# DUT.net
KiCad netlist of a schematic drawn in Altium Designer
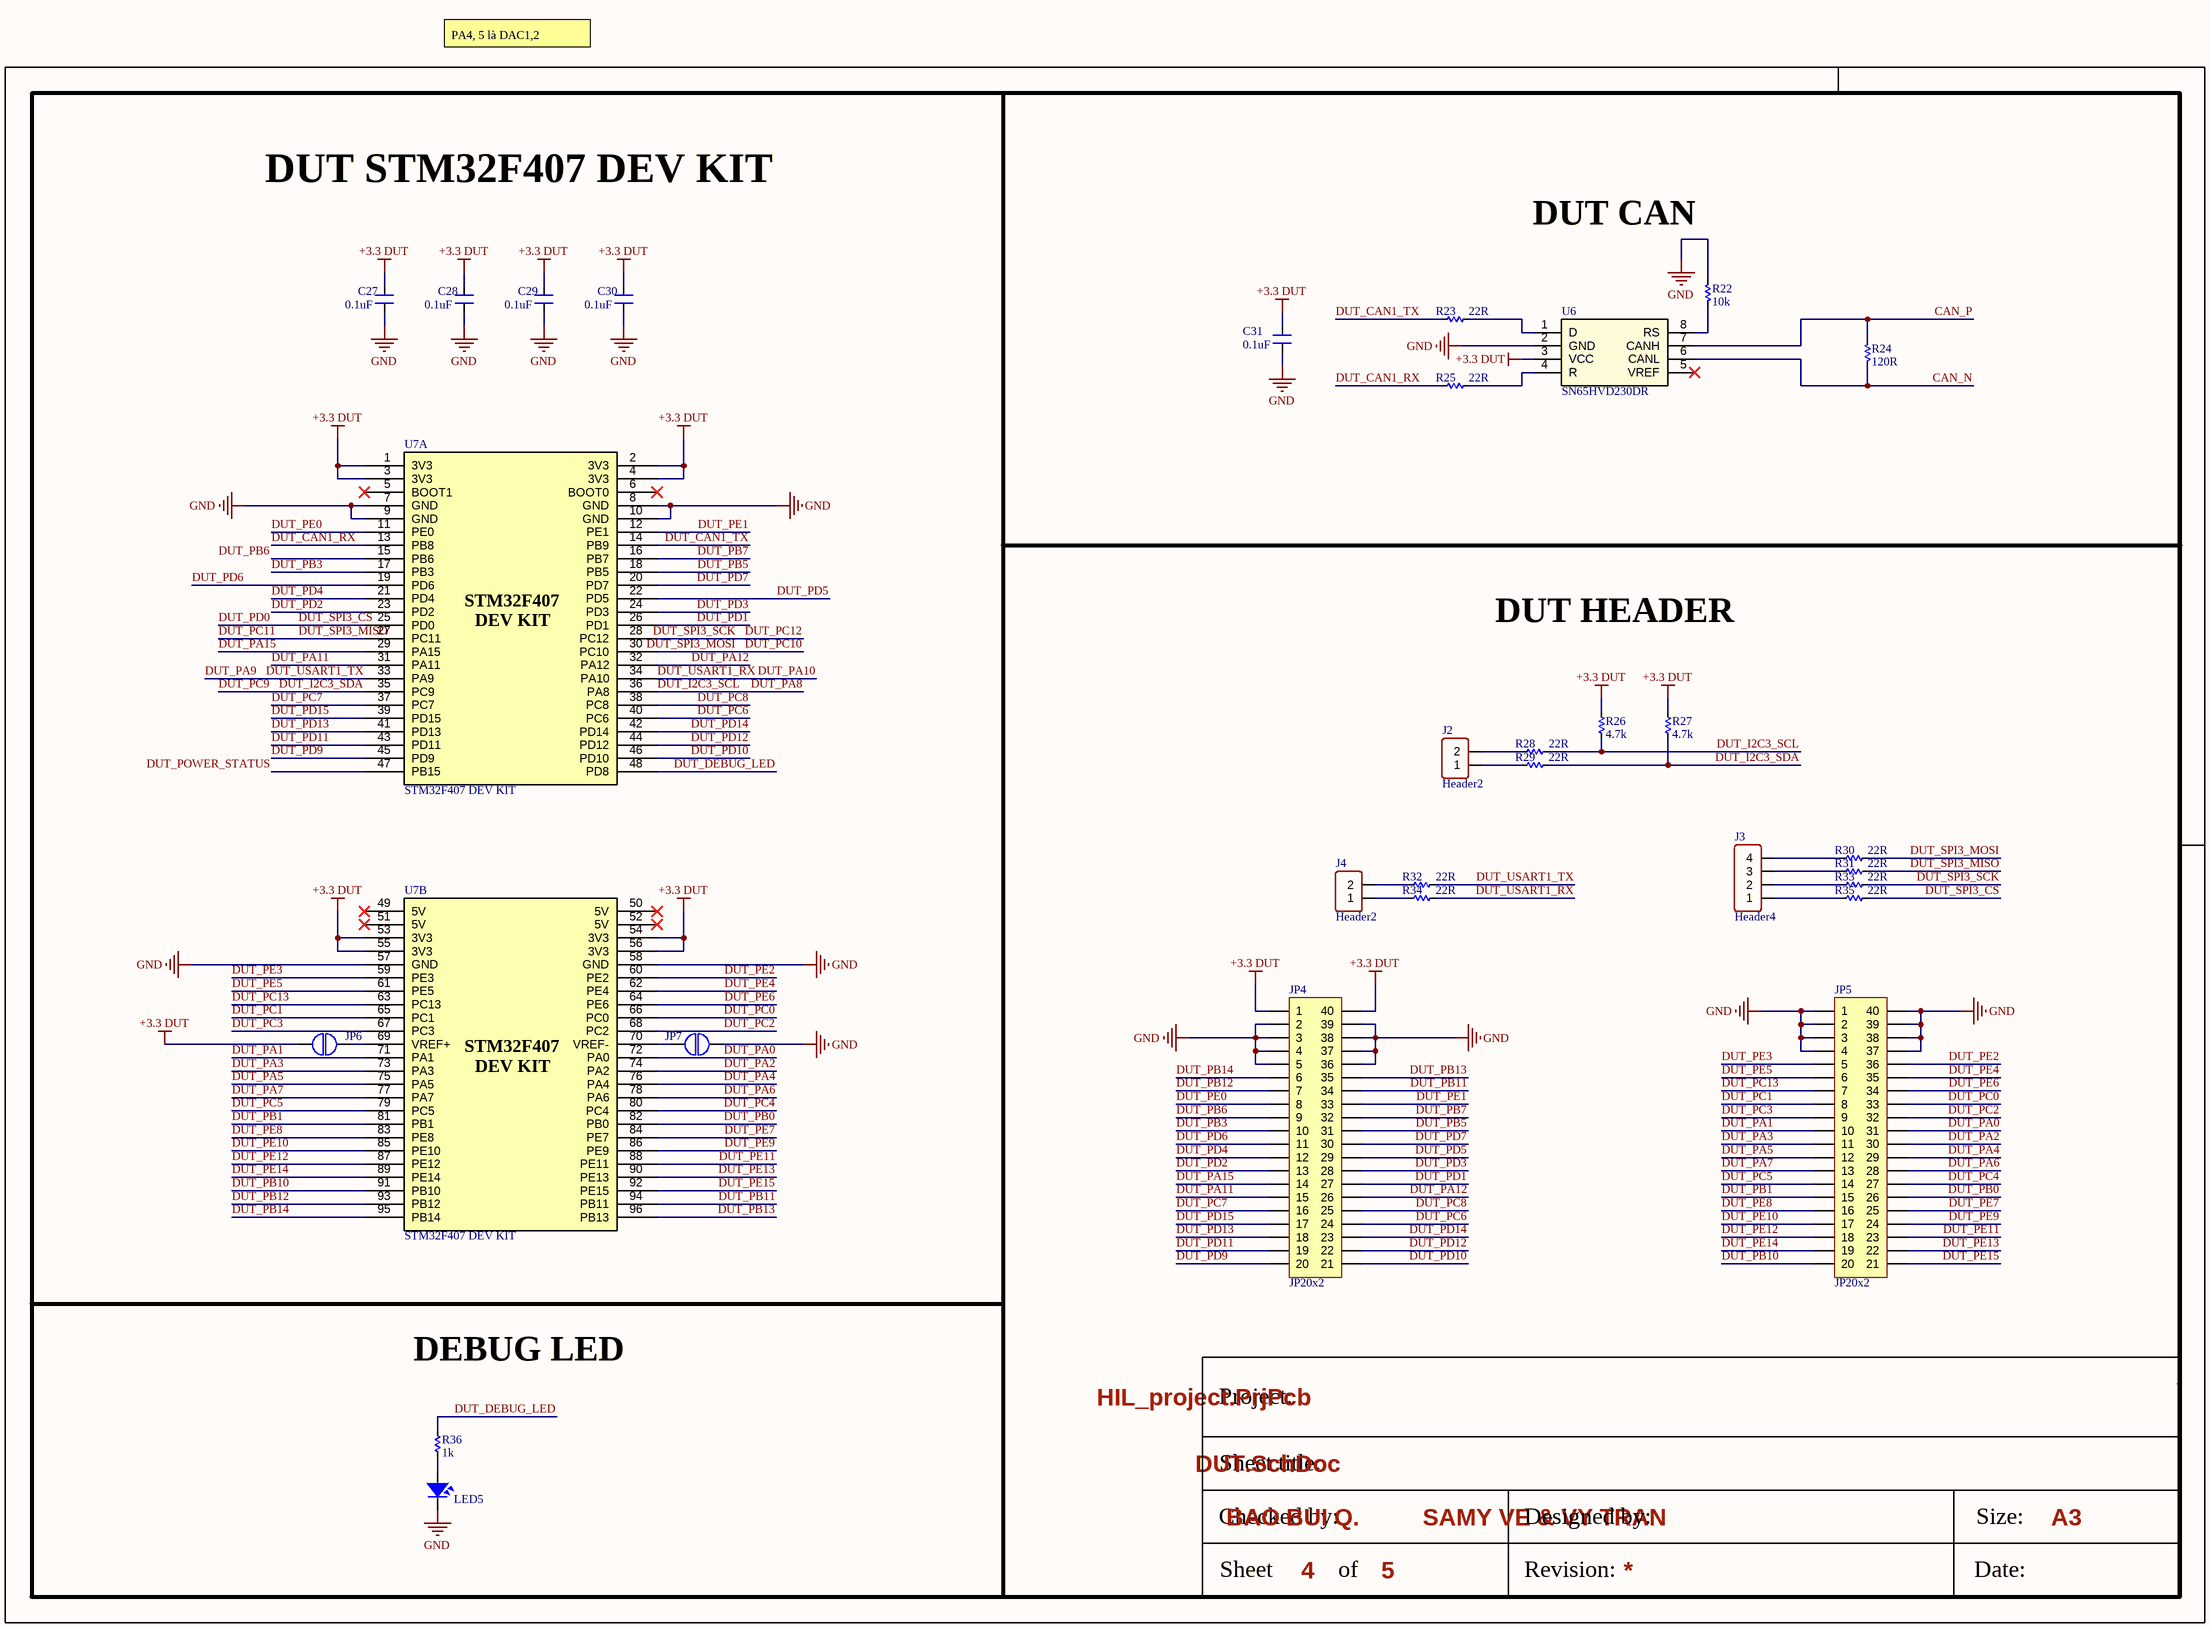
[diagram p0: DUT.SchDoc]

(export (version "E")
  (design (tool "Eeschema 10.0.6"))
  (components
    (comp (ref "C27") (value "0.1uF") (footprint "CN-SMD-0603") (libsource (lib "Library") (part "CN")))
    (comp (ref "C28") (value "0.1uF") (footprint "CN-SMD-0603") (libsource (lib "Library") (part "CN")))
    (comp (ref "C29") (value "0.1uF") (footprint "CN-SMD-0603") (libsource (lib "Library") (part "CN")))
    (comp (ref "C30") (value "0.1uF") (footprint "CN-SMD-0603") (libsource (lib "Library") (part "CN")))
    (comp (ref "C31") (value "0.1uF") (footprint "CN-SMD-0603") (libsource (lib "Library") (part "CN")))
    (comp (ref "J2")
      (value "Header2")
      (footprint "XH2.54-2-DIP")
      (description "Connector 2")
      (fields
        (field (name "MANUFACTURER") "Würth Elektronik eiSos GmbH")
        (field (name "PARTNO") "613002143121")
        (field (name "CREATED BY") "Karrer Zheng")
      )
      (libsource (lib "Library") (part "Header2"))
    )
    (comp (ref "J3")
      (value "Header4")
      (footprint "XH2.54-4-DIP")
      (description "Connector 4")
      (fields
        (field (name "MANUFACTURER") "Würth Elektronik eiSos GmbH")
        (field (name "PARTNO") "613002143121")
        (field (name "CREATED BY") "Karrer Zheng")
      )
      (libsource (lib "Library") (part "Header4"))
    )
    (comp (ref "J4")
      (value "Header2")
      (footprint "XH2.54-2-DIP")
      (description "Connector 2")
      (fields
        (field (name "MANUFACTURER") "Würth Elektronik eiSos GmbH")
        (field (name "PARTNO") "613002143121")
        (field (name "CREATED BY") "Karrer Zheng")
      )
      (libsource (lib "Library") (part "Header2"))
    )
    (comp (ref "JP4")
      (value "JP20x2")
      (footprint "JP20-D2T")
      (description "WR-PHD 2.54 mm Dual Socket Header")
      (fields
        (field (name "MANUFACTURER") "Würth Elektronik eiSos GmbH")
        (field (name "PARTNO") "61304021821")
        (field (name "CREATED BY") "Karrer Zheng")
      )
      (libsource (lib "Library") (part "JP20x2"))
    )
    (comp (ref "JP5")
      (value "JP20x2")
      (footprint "JP20-D2T")
      (description "WR-PHD 2.54 mm Dual Socket Header")
      (fields
        (field (name "MANUFACTURER") "Würth Elektronik eiSos GmbH")
        (field (name "PARTNO") "61304021821")
        (field (name "CREATED BY") "Karrer Zheng")
      )
      (libsource (lib "Library") (part "JP20x2"))
    )
    (comp (ref "JP6") (value "JUMP2") (footprint "Jump2") (libsource (lib "Library") (part "JUMP2")))
    (comp (ref "JP7") (value "JUMP2") (footprint "Jump2") (libsource (lib "Library") (part "JUMP2")))
    (comp (ref "LED5") (value "LED") (footprint "LED-0805-Red") (libsource (lib "Library") (part "LED SMD")))
    (comp (ref "R22")
      (value "10k")
      (footprint "RES-SMD-0603")
      (description "Resistor")
      (fields
        (field (name "MANUFACTURER") "Generic Components")
        (field (name "PUBLISHER") "Altium Hobart Technology Centre")
      )
      (libsource (lib "Library") (part "Res-SMD"))
    )
    (comp (ref "R23")
      (value "22R")
      (footprint "RES-SMD-0603")
      (description "Resistor")
      (fields
        (field (name "MANUFACTURER") "Generic Components")
        (field (name "PUBLISHER") "Altium Hobart Technology Centre")
      )
      (libsource (lib "Library") (part "Res-SMD"))
    )
    (comp (ref "R24")
      (value "120R")
      (footprint "RES-SMD-0603")
      (description "Resistor")
      (fields
        (field (name "MANUFACTURER") "Generic Components")
        (field (name "PUBLISHER") "Altium Hobart Technology Centre")
      )
      (libsource (lib "Library") (part "Res-SMD"))
    )
    (comp (ref "R25")
      (value "22R")
      (footprint "RES-SMD-0603")
      (description "Resistor")
      (fields
        (field (name "MANUFACTURER") "Generic Components")
        (field (name "PUBLISHER") "Altium Hobart Technology Centre")
      )
      (libsource (lib "Library") (part "Res-SMD"))
    )
    (comp (ref "R26")
      (value "4.7k")
      (footprint "RES-SMD-0603")
      (description "Resistor")
      (fields
        (field (name "MANUFACTURER") "Generic Components")
        (field (name "PUBLISHER") "Altium Hobart Technology Centre")
      )
      (libsource (lib "Library") (part "Res-SMD"))
    )
    (comp (ref "R27")
      (value "4.7k")
      (footprint "RES-SMD-0603")
      (description "Resistor")
      (fields
        (field (name "MANUFACTURER") "Generic Components")
        (field (name "PUBLISHER") "Altium Hobart Technology Centre")
      )
      (libsource (lib "Library") (part "Res-SMD"))
    )
    (comp (ref "R28")
      (value "22R")
      (footprint "RES-SMD-0603")
      (description "Resistor")
      (fields
        (field (name "MANUFACTURER") "Generic Components")
        (field (name "PUBLISHER") "Altium Hobart Technology Centre")
      )
      (libsource (lib "Library") (part "Res-SMD"))
    )
    (comp (ref "R29")
      (value "22R")
      (footprint "RES-SMD-0603")
      (description "Resistor")
      (fields
        (field (name "MANUFACTURER") "Generic Components")
        (field (name "PUBLISHER") "Altium Hobart Technology Centre")
      )
      (libsource (lib "Library") (part "Res-SMD"))
    )
    (comp (ref "R30")
      (value "22R")
      (footprint "RES-SMD-0603")
      (description "Resistor")
      (fields
        (field (name "MANUFACTURER") "Generic Components")
        (field (name "PUBLISHER") "Altium Hobart Technology Centre")
      )
      (libsource (lib "Library") (part "Res-SMD"))
    )
    (comp (ref "R31")
      (value "22R")
      (footprint "RES-SMD-0603")
      (description "Resistor")
      (fields
        (field (name "MANUFACTURER") "Generic Components")
        (field (name "PUBLISHER") "Altium Hobart Technology Centre")
      )
      (libsource (lib "Library") (part "Res-SMD"))
    )
    (comp (ref "R32")
      (value "22R")
      (footprint "RES-SMD-0603")
      (description "Resistor")
      (fields
        (field (name "MANUFACTURER") "Generic Components")
        (field (name "PUBLISHER") "Altium Hobart Technology Centre")
      )
      (libsource (lib "Library") (part "Res-SMD"))
    )
    (comp (ref "R33")
      (value "22R")
      (footprint "RES-SMD-0603")
      (description "Resistor")
      (fields
        (field (name "MANUFACTURER") "Generic Components")
        (field (name "PUBLISHER") "Altium Hobart Technology Centre")
      )
      (libsource (lib "Library") (part "Res-SMD"))
    )
    (comp (ref "R34")
      (value "22R")
      (footprint "RES-SMD-0603")
      (description "Resistor")
      (fields
        (field (name "MANUFACTURER") "Generic Components")
        (field (name "PUBLISHER") "Altium Hobart Technology Centre")
      )
      (libsource (lib "Library") (part "Res-SMD"))
    )
    (comp (ref "R35")
      (value "22R")
      (footprint "RES-SMD-0603")
      (description "Resistor")
      (fields
        (field (name "MANUFACTURER") "Generic Components")
        (field (name "PUBLISHER") "Altium Hobart Technology Centre")
      )
      (libsource (lib "Library") (part "Res-SMD"))
    )
    (comp (ref "R36")
      (value "1k")
      (footprint "RES-SMD-0603")
      (description "Resistor")
      (fields
        (field (name "MANUFACTURER") "Generic Components")
        (field (name "PUBLISHER") "Altium Hobart Technology Centre")
      )
      (libsource (lib "Library") (part "Res-SMD"))
    )
    (comp (ref "U6")
      (value "SN65HVD230DR")
      (footprint "SO8")
      (description "IC TRANSCEIVER HALF 1/1 8SOIC")
      (libsource (lib "Library") (part "SN65HVD251DR"))
    )
    (comp (ref "U7")
      (value "STM32F407 DEV KIT")
      (footprint "STM32F407 DEV KIT")
      (libsource (lib "Library") (part "STM32F407 DEV KIT"))
    )
  )
  (nets
    (net (code "1") (name "+3.3 DUT") (class "Default")
      (node (ref "C27") (pin "1") (pinfunction "1_1") (pintype "passive"))
      (node (ref "C28") (pin "1") (pinfunction "1_1") (pintype "passive"))
      (node (ref "C29") (pin "1") (pinfunction "1_1") (pintype "passive"))
      (node (ref "C30") (pin "1") (pinfunction "1_1") (pintype "passive"))
      (node (ref "C31") (pin "1") (pinfunction "1_1") (pintype "passive"))
      (node (ref "JP4") (pin "1") (pinfunction "1_1") (pintype "passive"))
      (node (ref "JP4") (pin "40") (pinfunction "40_40") (pintype "passive"))
      (node (ref "JP6") (pin "1") (pinfunction "1_1") (pintype "passive"))
      (node (ref "R26") (pin "1") (pinfunction "1_1") (pintype "passive"))
      (node (ref "R27") (pin "1") (pinfunction "1_1") (pintype "passive"))
      (node (ref "U6") (pin "3") (pinfunction "VCC_3") (pintype "power_in"))
      (node (ref "U7") (pin "1") (pinfunction "3V3_1") (pintype "passive"))
      (node (ref "U7") (pin "2") (pinfunction "3V3_2") (pintype "passive"))
      (node (ref "U7") (pin "3") (pinfunction "3V3_3") (pintype "passive"))
      (node (ref "U7") (pin "4") (pinfunction "3V3_4") (pintype "passive"))
      (node (ref "U7") (pin "53") (pinfunction "3V3_53") (pintype "passive"))
      (node (ref "U7") (pin "54") (pinfunction "3V3_54") (pintype "passive"))
      (node (ref "U7") (pin "55") (pinfunction "3V3_55") (pintype "passive"))
      (node (ref "U7") (pin "56") (pinfunction "3V3_56") (pintype "passive"))
    )
    (net (code "2") (name "/CAN_N") (class "Default")
      (node (ref "R24") (pin "2") (pinfunction "2_2") (pintype "passive"))
      (node (ref "U6") (pin "6") (pinfunction "CANL_6") (pintype "power_in"))
    )
    (net (code "3") (name "/CAN_P") (class "Default")
      (node (ref "R24") (pin "1") (pinfunction "1_1") (pintype "passive"))
      (node (ref "U6") (pin "7") (pinfunction "CANH_7") (pintype "power_in"))
    )
    (net (code "4") (name "/DUT_CAN1_RX") (class "Default")
      (node (ref "R25") (pin "2") (pinfunction "2_2") (pintype "passive"))
      (node (ref "U7") (pin "13") (pinfunction "PB8_13") (pintype "passive"))
    )
    (net (code "5") (name "/DUT_CAN1_TX") (class "Default")
      (node (ref "R23") (pin "2") (pinfunction "2_2") (pintype "passive"))
      (node (ref "U7") (pin "14") (pinfunction "PB9_14") (pintype "passive"))
    )
    (net (code "6") (name "/DUT_DEBUG_LED") (class "Default")
      (node (ref "R36") (pin "2") (pinfunction "2_2") (pintype "passive"))
      (node (ref "U7") (pin "48") (pinfunction "PD8_48") (pintype "passive"))
    )
    (net (code "7") (name "/DUT_I2C3_SCL") (class "Default")
      (node (ref "R26") (pin "2") (pinfunction "2_2") (pintype "passive"))
      (node (ref "R28") (pin "1") (pinfunction "1_1") (pintype "passive"))
      (node (ref "U7") (pin "36") (pinfunction "PA8_36") (pintype "passive"))
    )
    (net (code "8") (name "/DUT_I2C3_SDA") (class "Default")
      (node (ref "R27") (pin "2") (pinfunction "2_2") (pintype "passive"))
      (node (ref "R29") (pin "1") (pinfunction "1_1") (pintype "passive"))
      (node (ref "U7") (pin "35") (pinfunction "PC9_35") (pintype "passive"))
    )
    (net (code "9") (name "/DUT_PA0") (class "Default")
      (node (ref "JP5") (pin "31") (pinfunction "31_31") (pintype "passive"))
      (node (ref "U7") (pin "72") (pinfunction "PA0_72") (pintype "passive"))
    )
    (net (code "10") (name "/DUT_PA1") (class "Default")
      (node (ref "JP5") (pin "10") (pinfunction "10_10") (pintype "passive"))
      (node (ref "U7") (pin "71") (pinfunction "PA1_71") (pintype "passive"))
    )
    (net (code "11") (name "/DUT_PA2") (class "Default")
      (node (ref "JP5") (pin "30") (pinfunction "30_30") (pintype "passive"))
      (node (ref "U7") (pin "74") (pinfunction "PA2_74") (pintype "passive"))
    )
    (net (code "12") (name "/DUT_PA3") (class "Default")
      (node (ref "JP5") (pin "11") (pinfunction "11_11") (pintype "passive"))
      (node (ref "U7") (pin "73") (pinfunction "PA3_73") (pintype "passive"))
    )
    (net (code "13") (name "/DUT_PA4") (class "Default")
      (node (ref "JP5") (pin "29") (pinfunction "29_29") (pintype "passive"))
      (node (ref "U7") (pin "76") (pinfunction "PA4_76") (pintype "passive"))
    )
    (net (code "14") (name "/DUT_PA5") (class "Default")
      (node (ref "JP5") (pin "12") (pinfunction "12_12") (pintype "passive"))
      (node (ref "U7") (pin "75") (pinfunction "PA5_75") (pintype "passive"))
    )
    (net (code "15") (name "/DUT_PA6") (class "Default")
      (node (ref "JP5") (pin "28") (pinfunction "28_28") (pintype "passive"))
      (node (ref "U7") (pin "78") (pinfunction "PA6_78") (pintype "passive"))
    )
    (net (code "16") (name "/DUT_PA7") (class "Default")
      (node (ref "JP5") (pin "13") (pinfunction "13_13") (pintype "passive"))
      (node (ref "U7") (pin "77") (pinfunction "PA7_77") (pintype "passive"))
    )
    (net (code "17") (name "/DUT_PA9") (class "Default")
      (node (ref "R32") (pin "1") (pinfunction "1_1") (pintype "passive"))
      (node (ref "U7") (pin "33") (pinfunction "PA9_33") (pintype "passive"))
    )
    (net (code "18") (name "/DUT_PA10") (class "Default")
      (node (ref "R34") (pin "1") (pinfunction "1_1") (pintype "passive"))
      (node (ref "U7") (pin "34") (pinfunction "PA10_34") (pintype "passive"))
    )
    (net (code "19") (name "/DUT_PA11") (class "Default")
      (node (ref "JP4") (pin "15") (pinfunction "15_15") (pintype "passive"))
      (node (ref "U7") (pin "31") (pinfunction "PA11_31") (pintype "passive"))
    )
    (net (code "20") (name "/DUT_PA12") (class "Default")
      (node (ref "JP4") (pin "26") (pinfunction "26_26") (pintype "passive"))
      (node (ref "U7") (pin "32") (pinfunction "PA12_32") (pintype "passive"))
    )
    (net (code "21") (name "/DUT_PA15") (class "Default")
      (node (ref "JP4") (pin "14") (pinfunction "14_14") (pintype "passive"))
      (node (ref "U7") (pin "29") (pinfunction "PA15_29") (pintype "passive"))
    )
    (net (code "22") (name "/DUT_PB0") (class "Default")
      (node (ref "JP5") (pin "26") (pinfunction "26_26") (pintype "passive"))
      (node (ref "U7") (pin "82") (pinfunction "PB0_82") (pintype "passive"))
    )
    (net (code "23") (name "/DUT_PB1") (class "Default")
      (node (ref "JP5") (pin "15") (pinfunction "15_15") (pintype "passive"))
      (node (ref "U7") (pin "81") (pinfunction "PB1_81") (pintype "passive"))
    )
    (net (code "24") (name "/DUT_PB3") (class "Default")
      (node (ref "JP4") (pin "10") (pinfunction "10_10") (pintype "passive"))
      (node (ref "U7") (pin "17") (pinfunction "PB3_17") (pintype "passive"))
    )
    (net (code "25") (name "/DUT_PB5") (class "Default")
      (node (ref "JP4") (pin "31") (pinfunction "31_31") (pintype "passive"))
      (node (ref "U7") (pin "18") (pinfunction "PB5_18") (pintype "passive"))
    )
    (net (code "26") (name "/DUT_PB6") (class "Default")
      (node (ref "JP4") (pin "9") (pinfunction "9_9") (pintype "passive"))
      (node (ref "U7") (pin "15") (pinfunction "PB6_15") (pintype "passive"))
    )
    (net (code "27") (name "/DUT_PB7") (class "Default")
      (node (ref "JP4") (pin "32") (pinfunction "32_32") (pintype "passive"))
      (node (ref "U7") (pin "16") (pinfunction "PB7_16") (pintype "passive"))
    )
    (net (code "28") (name "/DUT_PB10") (class "Default")
      (node (ref "JP5") (pin "20") (pinfunction "20_20") (pintype "passive"))
      (node (ref "U7") (pin "91") (pinfunction "PB10_91") (pintype "passive"))
    )
    (net (code "29") (name "/DUT_PB11") (class "Default")
      (node (ref "JP4") (pin "34") (pinfunction "34_34") (pintype "passive"))
      (node (ref "U7") (pin "94") (pinfunction "PB11_94") (pintype "passive"))
    )
    (net (code "30") (name "/DUT_PB12") (class "Default")
      (node (ref "JP4") (pin "7") (pinfunction "7_7") (pintype "passive"))
      (node (ref "U7") (pin "93") (pinfunction "PB12_93") (pintype "passive"))
    )
    (net (code "31") (name "/DUT_PB13") (class "Default")
      (node (ref "JP4") (pin "35") (pinfunction "35_35") (pintype "passive"))
      (node (ref "U7") (pin "96") (pinfunction "PB13_96") (pintype "passive"))
    )
    (net (code "32") (name "/DUT_PB14") (class "Default")
      (node (ref "JP4") (pin "6") (pinfunction "6_6") (pintype "passive"))
      (node (ref "U7") (pin "95") (pinfunction "PB14_95") (pintype "passive"))
    )
    (net (code "33") (name "/DUT_PC0") (class "Default")
      (node (ref "JP5") (pin "33") (pinfunction "33_33") (pintype "passive"))
      (node (ref "U7") (pin "66") (pinfunction "PC0_66") (pintype "passive"))
    )
    (net (code "34") (name "/DUT_PC1") (class "Default")
      (node (ref "JP5") (pin "8") (pinfunction "8_8") (pintype "passive"))
      (node (ref "U7") (pin "65") (pinfunction "PC1_65") (pintype "passive"))
    )
    (net (code "35") (name "/DUT_PC2") (class "Default")
      (node (ref "JP5") (pin "32") (pinfunction "32_32") (pintype "passive"))
      (node (ref "U7") (pin "68") (pinfunction "PC2_68") (pintype "passive"))
    )
    (net (code "36") (name "/DUT_PC3") (class "Default")
      (node (ref "JP5") (pin "9") (pinfunction "9_9") (pintype "passive"))
      (node (ref "U7") (pin "67") (pinfunction "PC3_67") (pintype "passive"))
    )
    (net (code "37") (name "/DUT_PC4") (class "Default")
      (node (ref "JP5") (pin "27") (pinfunction "27_27") (pintype "passive"))
      (node (ref "U7") (pin "80") (pinfunction "PC4_80") (pintype "passive"))
    )
    (net (code "38") (name "/DUT_PC5") (class "Default")
      (node (ref "JP5") (pin "14") (pinfunction "14_14") (pintype "passive"))
      (node (ref "U7") (pin "79") (pinfunction "PC5_79") (pintype "passive"))
    )
    (net (code "39") (name "/DUT_PC6") (class "Default")
      (node (ref "JP4") (pin "24") (pinfunction "24_24") (pintype "passive"))
      (node (ref "U7") (pin "40") (pinfunction "PC6_40") (pintype "passive"))
    )
    (net (code "40") (name "/DUT_PC7") (class "Default")
      (node (ref "JP4") (pin "16") (pinfunction "16_16") (pintype "passive"))
      (node (ref "U7") (pin "37") (pinfunction "PC7_37") (pintype "passive"))
    )
    (net (code "41") (name "/DUT_PC8") (class "Default")
      (node (ref "JP4") (pin "25") (pinfunction "25_25") (pintype "passive"))
      (node (ref "U7") (pin "38") (pinfunction "PC8_38") (pintype "passive"))
    )
    (net (code "42") (name "/DUT_PC10") (class "Default")
      (node (ref "R30") (pin "1") (pinfunction "1_1") (pintype "passive"))
      (node (ref "U7") (pin "30") (pinfunction "PC10_30") (pintype "passive"))
    )
    (net (code "43") (name "/DUT_PC11") (class "Default")
      (node (ref "R31") (pin "1") (pinfunction "1_1") (pintype "passive"))
      (node (ref "U7") (pin "27") (pinfunction "PC11_27") (pintype "passive"))
    )
    (net (code "44") (name "/DUT_PC12") (class "Default")
      (node (ref "R33") (pin "1") (pinfunction "1_1") (pintype "passive"))
      (node (ref "U7") (pin "28") (pinfunction "PC12_28") (pintype "passive"))
    )
    (net (code "45") (name "/DUT_PC13") (class "Default")
      (node (ref "JP5") (pin "7") (pinfunction "7_7") (pintype "passive"))
      (node (ref "U7") (pin "63") (pinfunction "PC13_63") (pintype "passive"))
    )
    (net (code "46") (name "/DUT_PD0") (class "Default")
      (node (ref "R35") (pin "1") (pinfunction "1_1") (pintype "passive"))
      (node (ref "U7") (pin "25") (pinfunction "PD0_25") (pintype "passive"))
    )
    (net (code "47") (name "/DUT_PD1") (class "Default")
      (node (ref "JP4") (pin "27") (pinfunction "27_27") (pintype "passive"))
      (node (ref "U7") (pin "26") (pinfunction "PD1_26") (pintype "passive"))
    )
    (net (code "48") (name "/DUT_PD2") (class "Default")
      (node (ref "JP4") (pin "13") (pinfunction "13_13") (pintype "passive"))
      (node (ref "U7") (pin "23") (pinfunction "PD2_23") (pintype "passive"))
    )
    (net (code "49") (name "/DUT_PD3") (class "Default")
      (node (ref "JP4") (pin "28") (pinfunction "28_28") (pintype "passive"))
      (node (ref "U7") (pin "24") (pinfunction "PD3_24") (pintype "passive"))
    )
    (net (code "50") (name "/DUT_PD4") (class "Default")
      (node (ref "JP4") (pin "12") (pinfunction "12_12") (pintype "passive"))
      (node (ref "U7") (pin "21") (pinfunction "PD4_21") (pintype "passive"))
    )
    (net (code "51") (name "/DUT_PD5") (class "Default")
      (node (ref "JP4") (pin "29") (pinfunction "29_29") (pintype "passive"))
      (node (ref "U7") (pin "22") (pinfunction "PD5_22") (pintype "passive"))
    )
    (net (code "52") (name "/DUT_PD6") (class "Default")
      (node (ref "JP4") (pin "11") (pinfunction "11_11") (pintype "passive"))
      (node (ref "U7") (pin "19") (pinfunction "PD6_19") (pintype "passive"))
    )
    (net (code "53") (name "/DUT_PD7") (class "Default")
      (node (ref "JP4") (pin "30") (pinfunction "30_30") (pintype "passive"))
      (node (ref "U7") (pin "20") (pinfunction "PD7_20") (pintype "passive"))
    )
    (net (code "54") (name "/DUT_PD9") (class "Default")
      (node (ref "JP4") (pin "20") (pinfunction "20_20") (pintype "passive"))
      (node (ref "U7") (pin "45") (pinfunction "PD9_45") (pintype "passive"))
    )
    (net (code "55") (name "/DUT_PD10") (class "Default")
      (node (ref "JP4") (pin "21") (pinfunction "21_21") (pintype "passive"))
      (node (ref "U7") (pin "46") (pinfunction "PD10_46") (pintype "passive"))
    )
    (net (code "56") (name "/DUT_PD11") (class "Default")
      (node (ref "JP4") (pin "19") (pinfunction "19_19") (pintype "passive"))
      (node (ref "U7") (pin "43") (pinfunction "PD11_43") (pintype "passive"))
    )
    (net (code "57") (name "/DUT_PD12") (class "Default")
      (node (ref "JP4") (pin "22") (pinfunction "22_22") (pintype "passive"))
      (node (ref "U7") (pin "44") (pinfunction "PD12_44") (pintype "passive"))
    )
    (net (code "58") (name "/DUT_PD13") (class "Default")
      (node (ref "JP4") (pin "18") (pinfunction "18_18") (pintype "passive"))
      (node (ref "U7") (pin "41") (pinfunction "PD13_41") (pintype "passive"))
    )
    (net (code "59") (name "/DUT_PD14") (class "Default")
      (node (ref "JP4") (pin "23") (pinfunction "23_23") (pintype "passive"))
      (node (ref "U7") (pin "42") (pinfunction "PD14_42") (pintype "passive"))
    )
    (net (code "60") (name "/DUT_PD15") (class "Default")
      (node (ref "JP4") (pin "17") (pinfunction "17_17") (pintype "passive"))
      (node (ref "U7") (pin "39") (pinfunction "PD15_39") (pintype "passive"))
    )
    (net (code "61") (name "/DUT_PE0") (class "Default")
      (node (ref "JP4") (pin "8") (pinfunction "8_8") (pintype "passive"))
      (node (ref "U7") (pin "11") (pinfunction "PE0_11") (pintype "passive"))
    )
    (net (code "62") (name "/DUT_PE1") (class "Default")
      (node (ref "JP4") (pin "33") (pinfunction "33_33") (pintype "passive"))
      (node (ref "U7") (pin "12") (pinfunction "PE1_12") (pintype "passive"))
    )
    (net (code "63") (name "/DUT_PE2") (class "Default")
      (node (ref "JP5") (pin "36") (pinfunction "36_36") (pintype "passive"))
      (node (ref "U7") (pin "60") (pinfunction "PE2_60") (pintype "passive"))
    )
    (net (code "64") (name "/DUT_PE3") (class "Default")
      (node (ref "JP5") (pin "5") (pinfunction "5_5") (pintype "passive"))
      (node (ref "U7") (pin "59") (pinfunction "PE3_59") (pintype "passive"))
    )
    (net (code "65") (name "/DUT_PE4") (class "Default")
      (node (ref "JP5") (pin "35") (pinfunction "35_35") (pintype "passive"))
      (node (ref "U7") (pin "62") (pinfunction "PE4_62") (pintype "passive"))
    )
    (net (code "66") (name "/DUT_PE5") (class "Default")
      (node (ref "JP5") (pin "6") (pinfunction "6_6") (pintype "passive"))
      (node (ref "U7") (pin "61") (pinfunction "PE5_61") (pintype "passive"))
    )
    (net (code "67") (name "/DUT_PE6") (class "Default")
      (node (ref "JP5") (pin "34") (pinfunction "34_34") (pintype "passive"))
      (node (ref "U7") (pin "64") (pinfunction "PE6_64") (pintype "passive"))
    )
    (net (code "68") (name "/DUT_PE7") (class "Default")
      (node (ref "JP5") (pin "25") (pinfunction "25_25") (pintype "passive"))
      (node (ref "U7") (pin "84") (pinfunction "PE7_84") (pintype "passive"))
    )
    (net (code "69") (name "/DUT_PE8") (class "Default")
      (node (ref "JP5") (pin "16") (pinfunction "16_16") (pintype "passive"))
      (node (ref "U7") (pin "83") (pinfunction "PE8_83") (pintype "passive"))
    )
    (net (code "70") (name "/DUT_PE9") (class "Default")
      (node (ref "JP5") (pin "24") (pinfunction "24_24") (pintype "passive"))
      (node (ref "U7") (pin "86") (pinfunction "PE9_86") (pintype "passive"))
    )
    (net (code "71") (name "/DUT_PE10") (class "Default")
      (node (ref "JP5") (pin "17") (pinfunction "17_17") (pintype "passive"))
      (node (ref "U7") (pin "85") (pinfunction "PE10_85") (pintype "passive"))
    )
    (net (code "72") (name "/DUT_PE11") (class "Default")
      (node (ref "JP5") (pin "23") (pinfunction "23_23") (pintype "passive"))
      (node (ref "U7") (pin "88") (pinfunction "PE11_88") (pintype "passive"))
    )
    (net (code "73") (name "/DUT_PE12") (class "Default")
      (node (ref "JP5") (pin "18") (pinfunction "18_18") (pintype "passive"))
      (node (ref "U7") (pin "87") (pinfunction "PE12_87") (pintype "passive"))
    )
    (net (code "74") (name "/DUT_PE13") (class "Default")
      (node (ref "JP5") (pin "22") (pinfunction "22_22") (pintype "passive"))
      (node (ref "U7") (pin "90") (pinfunction "PE13_90") (pintype "passive"))
    )
    (net (code "75") (name "/DUT_PE14") (class "Default")
      (node (ref "JP5") (pin "19") (pinfunction "19_19") (pintype "passive"))
      (node (ref "U7") (pin "89") (pinfunction "PE14_89") (pintype "passive"))
    )
    (net (code "76") (name "/DUT_PE15") (class "Default")
      (node (ref "JP5") (pin "21") (pinfunction "21_21") (pintype "passive"))
      (node (ref "U7") (pin "92") (pinfunction "PE15_92") (pintype "passive"))
    )
    (net (code "77") (name "/DUT_POWER_STATUS") (class "Default")
      (node (ref "U7") (pin "47") (pinfunction "PB15_47") (pintype "passive"))
    )
    (net (code "78") (name "GND") (class "Default")
      (node (ref "C27") (pin "2") (pinfunction "2_2") (pintype "passive"))
      (node (ref "C28") (pin "2") (pinfunction "2_2") (pintype "passive"))
      (node (ref "C29") (pin "2") (pinfunction "2_2") (pintype "passive"))
      (node (ref "C30") (pin "2") (pinfunction "2_2") (pintype "passive"))
      (node (ref "C31") (pin "2") (pinfunction "2_2") (pintype "passive"))
      (node (ref "JP4") (pin "2") (pinfunction "2_2") (pintype "passive"))
      (node (ref "JP4") (pin "3") (pinfunction "3_3") (pintype "passive"))
      (node (ref "JP4") (pin "36") (pinfunction "36_36") (pintype "passive"))
      (node (ref "JP4") (pin "37") (pinfunction "37_37") (pintype "passive"))
      (node (ref "JP4") (pin "38") (pinfunction "38_38") (pintype "passive"))
      (node (ref "JP4") (pin "39") (pinfunction "39_39") (pintype "passive"))
      (node (ref "JP4") (pin "4") (pinfunction "4_4") (pintype "passive"))
      (node (ref "JP4") (pin "5") (pinfunction "5_5") (pintype "passive"))
      (node (ref "JP5") (pin "1") (pinfunction "1_1") (pintype "passive"))
      (node (ref "JP5") (pin "2") (pinfunction "2_2") (pintype "passive"))
      (node (ref "JP5") (pin "3") (pinfunction "3_3") (pintype "passive"))
      (node (ref "JP5") (pin "37") (pinfunction "37_37") (pintype "passive"))
      (node (ref "JP5") (pin "38") (pinfunction "38_38") (pintype "passive"))
      (node (ref "JP5") (pin "39") (pinfunction "39_39") (pintype "passive"))
      (node (ref "JP5") (pin "4") (pinfunction "4_4") (pintype "passive"))
      (node (ref "JP5") (pin "40") (pinfunction "40_40") (pintype "passive"))
      (node (ref "JP7") (pin "2") (pinfunction "2_2") (pintype "passive"))
      (node (ref "LED5") (pin "2") (pinfunction "2_2") (pintype "passive"))
      (node (ref "R22") (pin "1") (pinfunction "1_1") (pintype "passive"))
      (node (ref "U6") (pin "2") (pinfunction "GND_2") (pintype "power_in"))
      (node (ref "U7") (pin "10") (pinfunction "GND_10") (pintype "passive"))
      (node (ref "U7") (pin "57") (pinfunction "GND_57") (pintype "passive"))
      (node (ref "U7") (pin "58") (pinfunction "GND_58") (pintype "passive"))
      (node (ref "U7") (pin "7") (pinfunction "GND_7") (pintype "passive"))
      (node (ref "U7") (pin "8") (pinfunction "GND_8") (pintype "passive"))
      (node (ref "U7") (pin "9") (pinfunction "GND_9") (pintype "passive"))
    )
    (net (code "79") (name "Net-(J2-Pad1)") (class "Default")
      (node (ref "J2") (pin "1") (pinfunction "1_1") (pintype "passive"))
      (node (ref "R29") (pin "2") (pinfunction "2_2") (pintype "passive"))
    )
    (net (code "80") (name "Net-(J2-Pad2)") (class "Default")
      (node (ref "J2") (pin "2") (pinfunction "2_2") (pintype "passive"))
      (node (ref "R28") (pin "2") (pinfunction "2_2") (pintype "passive"))
    )
    (net (code "81") (name "Net-(J3-Pad1)") (class "Default")
      (node (ref "J3") (pin "1") (pinfunction "1_1") (pintype "passive"))
      (node (ref "R35") (pin "2") (pinfunction "2_2") (pintype "passive"))
    )
    (net (code "82") (name "Net-(J3-Pad2)") (class "Default")
      (node (ref "J3") (pin "2") (pinfunction "2_2") (pintype "passive"))
      (node (ref "R33") (pin "2") (pinfunction "2_2") (pintype "passive"))
    )
    (net (code "83") (name "Net-(J3-Pad3)") (class "Default")
      (node (ref "J3") (pin "3") (pinfunction "3_3") (pintype "passive"))
      (node (ref "R31") (pin "2") (pinfunction "2_2") (pintype "passive"))
    )
    (net (code "84") (name "Net-(J3-Pad4)") (class "Default")
      (node (ref "J3") (pin "4") (pinfunction "4_4") (pintype "passive"))
      (node (ref "R30") (pin "2") (pinfunction "2_2") (pintype "passive"))
    )
    (net (code "85") (name "Net-(J4-Pad1)") (class "Default")
      (node (ref "J4") (pin "1") (pinfunction "1_1") (pintype "passive"))
      (node (ref "R34") (pin "2") (pinfunction "2_2") (pintype "passive"))
    )
    (net (code "86") (name "Net-(J4-Pad2)") (class "Default")
      (node (ref "J4") (pin "2") (pinfunction "2_2") (pintype "passive"))
      (node (ref "R32") (pin "2") (pinfunction "2_2") (pintype "passive"))
    )
    (net (code "87") (name "Net-(LED5-Pad1)") (class "Default")
      (node (ref "LED5") (pin "1") (pinfunction "1_1") (pintype "passive"))
      (node (ref "R36") (pin "1") (pinfunction "1_1") (pintype "passive"))
    )
    (net (code "88") (name "Net-(U6-D)") (class "Default")
      (node (ref "R23") (pin "1") (pinfunction "1_1") (pintype "passive"))
      (node (ref "U6") (pin "1") (pinfunction "D_1") (pintype "power_in"))
    )
    (net (code "89") (name "Net-(U6-R)") (class "Default")
      (node (ref "R25") (pin "1") (pinfunction "1_1") (pintype "passive"))
      (node (ref "U6") (pin "4") (pinfunction "R_4") (pintype "power_in"))
    )
    (net (code "90") (name "Net-(U6-RS)") (class "Default")
      (node (ref "R22") (pin "2") (pinfunction "2_2") (pintype "passive"))
      (node (ref "U6") (pin "8") (pinfunction "RS_8") (pintype "power_in"))
    )
    (net (code "91") (name "Net-(U7B-VREF+)") (class "Default")
      (node (ref "JP6") (pin "2") (pinfunction "2_2") (pintype "passive"))
      (node (ref "U7") (pin "69") (pinfunction "VREF+_69") (pintype "passive"))
    )
    (net (code "92") (name "Net-(U7B-VREF-)") (class "Default")
      (node (ref "JP7") (pin "1") (pinfunction "1_1") (pintype "passive"))
      (node (ref "U7") (pin "70") (pinfunction "VREF-_70") (pintype "passive"))
    )
    (net (code "93") (name "unconnected-(U6-VREF-Pad5)") (class "Default")
      (node (ref "U6") (pin "5") (pinfunction "VREF_5") (pintype "power_in+no_connect"))
    )
    (net (code "94") (name "unconnected-(U7A-BOOT0-Pad6)") (class "Default")
      (node (ref "U7") (pin "6") (pinfunction "BOOT0_6") (pintype "passive+no_connect"))
    )
    (net (code "95") (name "unconnected-(U7A-BOOT1-Pad5)") (class "Default")
      (node (ref "U7") (pin "5") (pinfunction "BOOT1_5") (pintype "passive+no_connect"))
    )
    (net (code "96") (name "unconnected-(U7B-5V-Pad49)") (class "Default")
      (node (ref "U7") (pin "49") (pinfunction "5V_49") (pintype "passive+no_connect"))
    )
    (net (code "97") (name "unconnected-(U7B-5V-Pad50)") (class "Default")
      (node (ref "U7") (pin "50") (pinfunction "5V_50") (pintype "passive+no_connect"))
    )
    (net (code "98") (name "unconnected-(U7B-5V-Pad51)") (class "Default")
      (node (ref "U7") (pin "51") (pinfunction "5V_51") (pintype "passive+no_connect"))
    )
    (net (code "99") (name "unconnected-(U7B-5V-Pad52)") (class "Default")
      (node (ref "U7") (pin "52") (pinfunction "5V_52") (pintype "passive+no_connect"))
    )
  )
)
